# 2023-08-02_LVMi_Thermistors.net
KiCad netlist of a schematic drawn in EAGLE
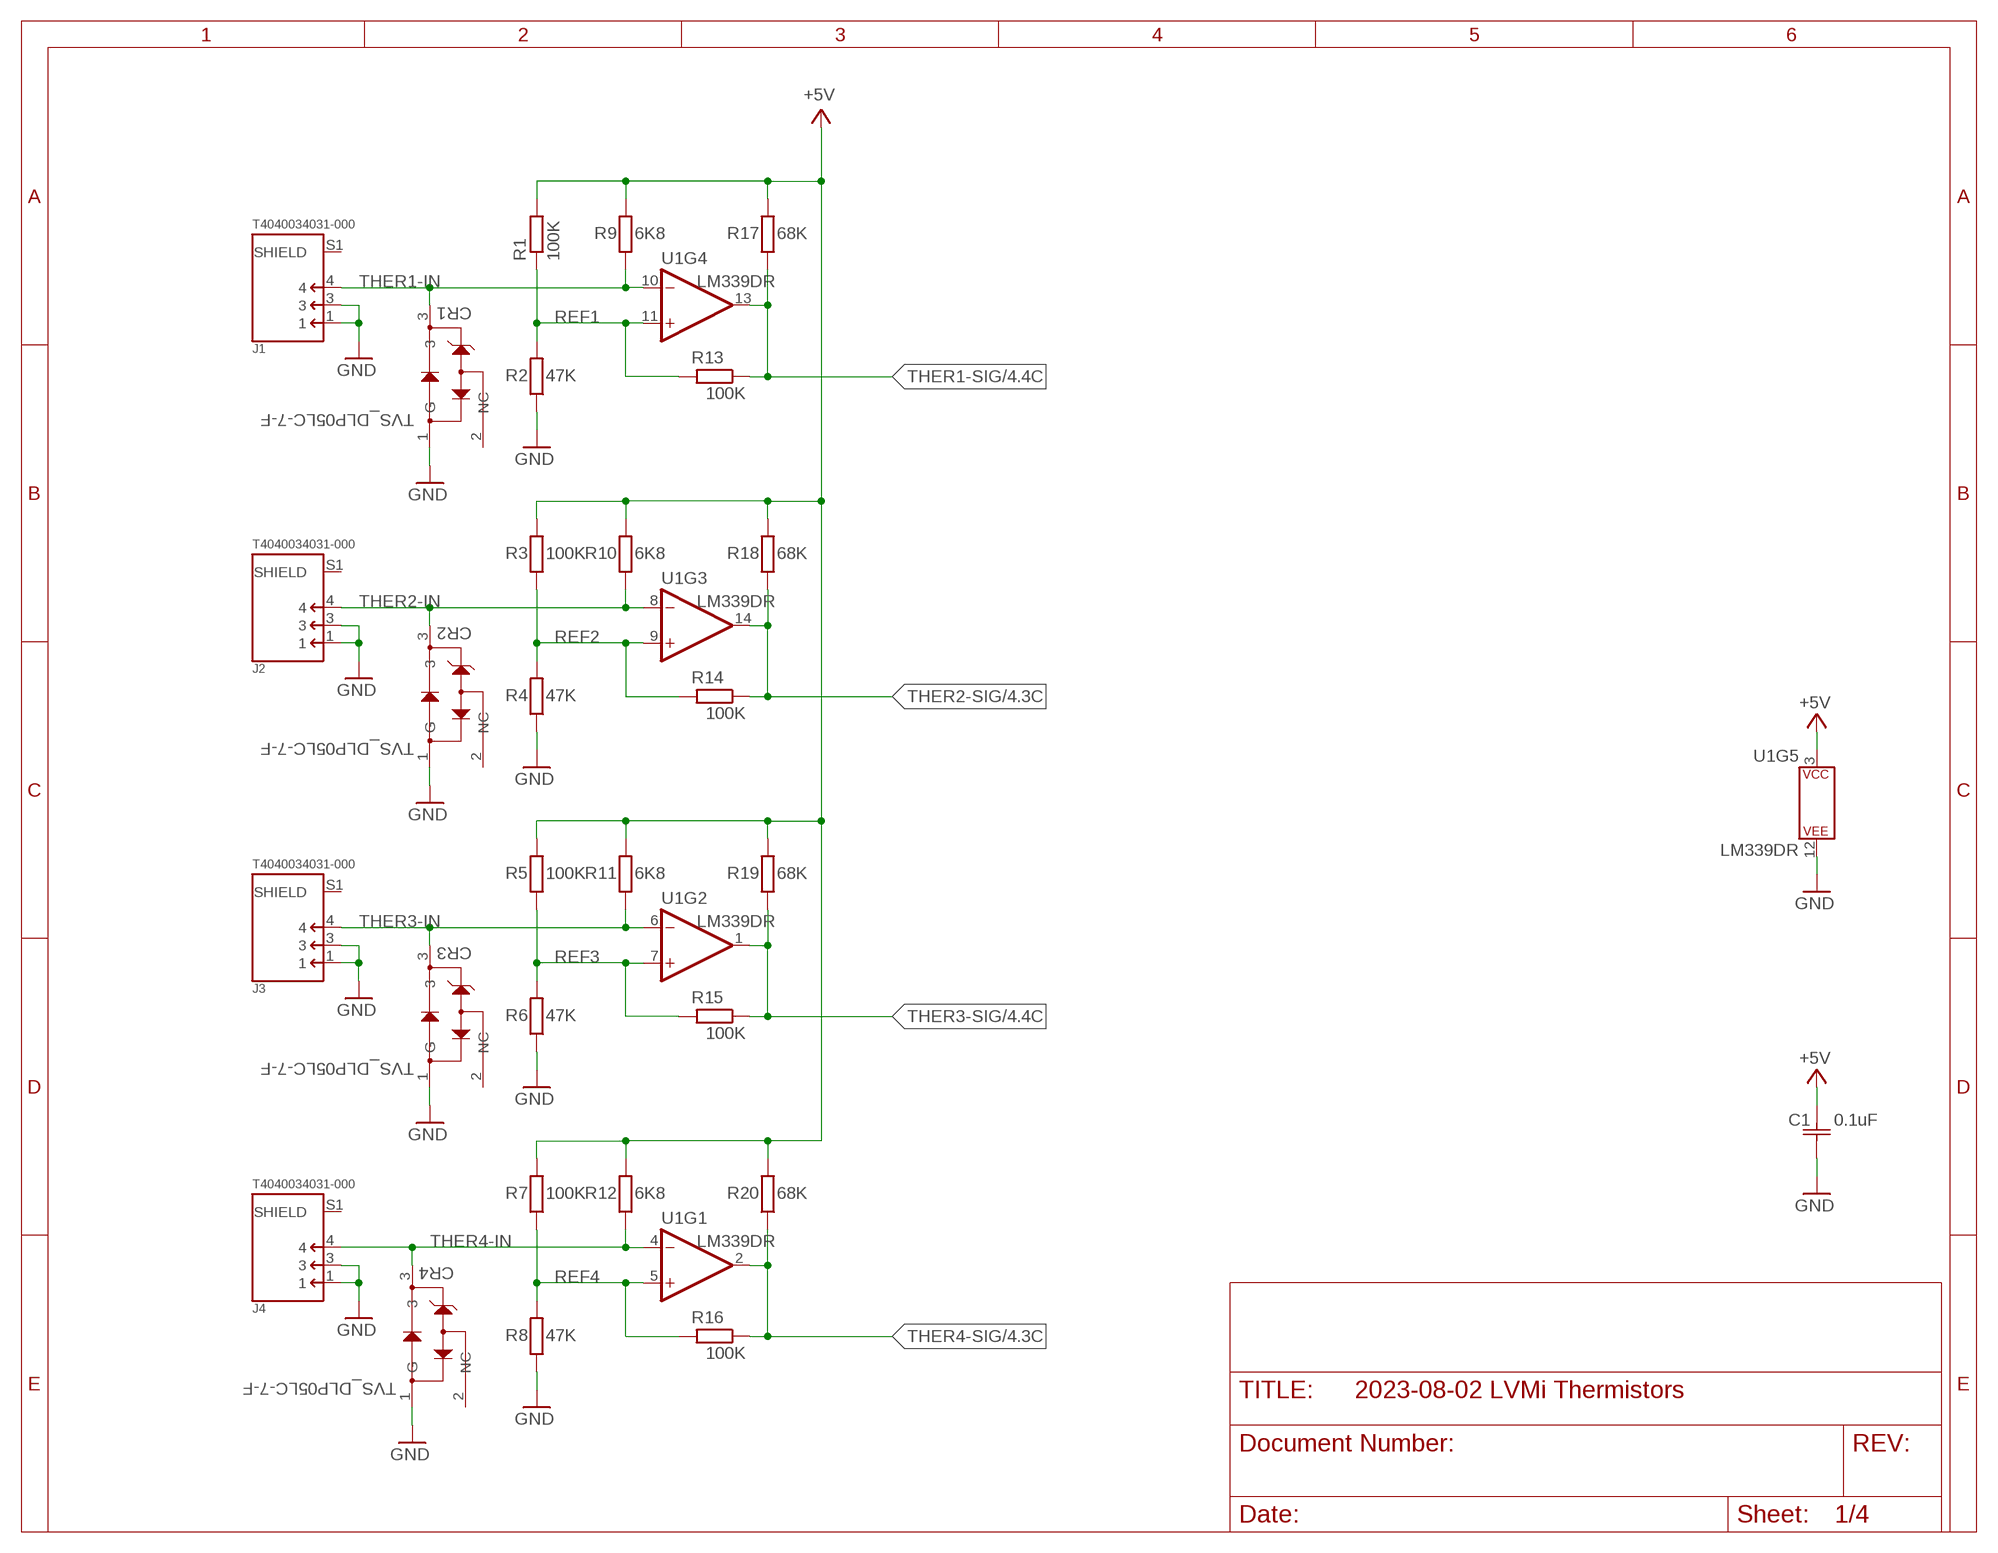
[diagram p0: schematic, sheet 1]
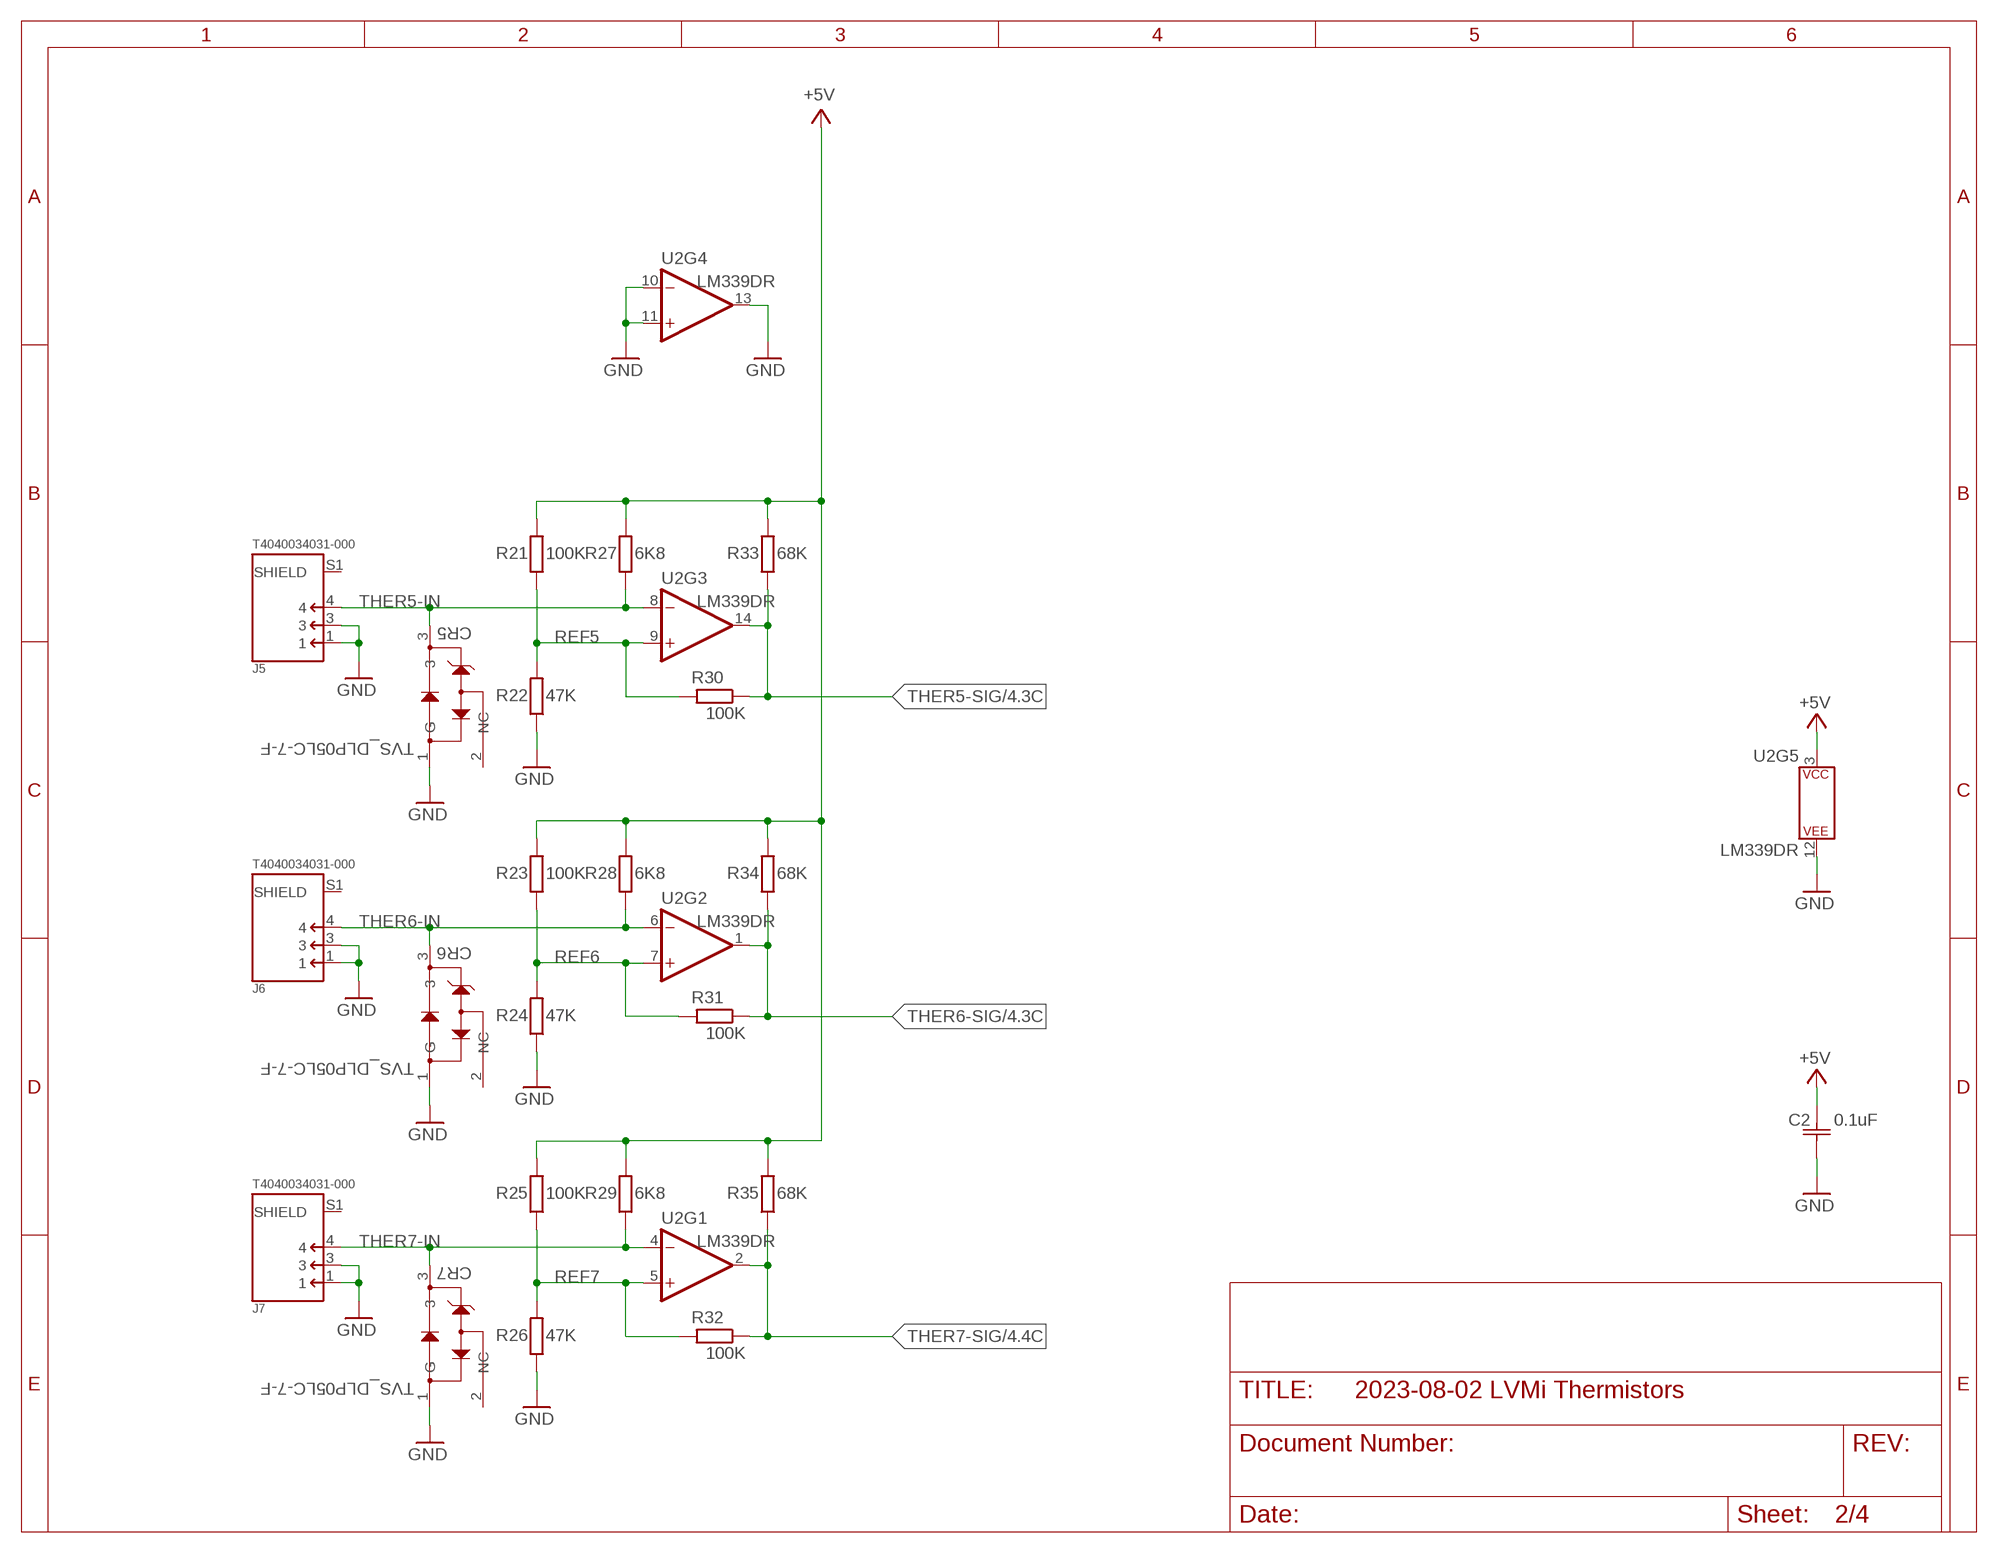
[diagram p1: schematic, sheet 2]
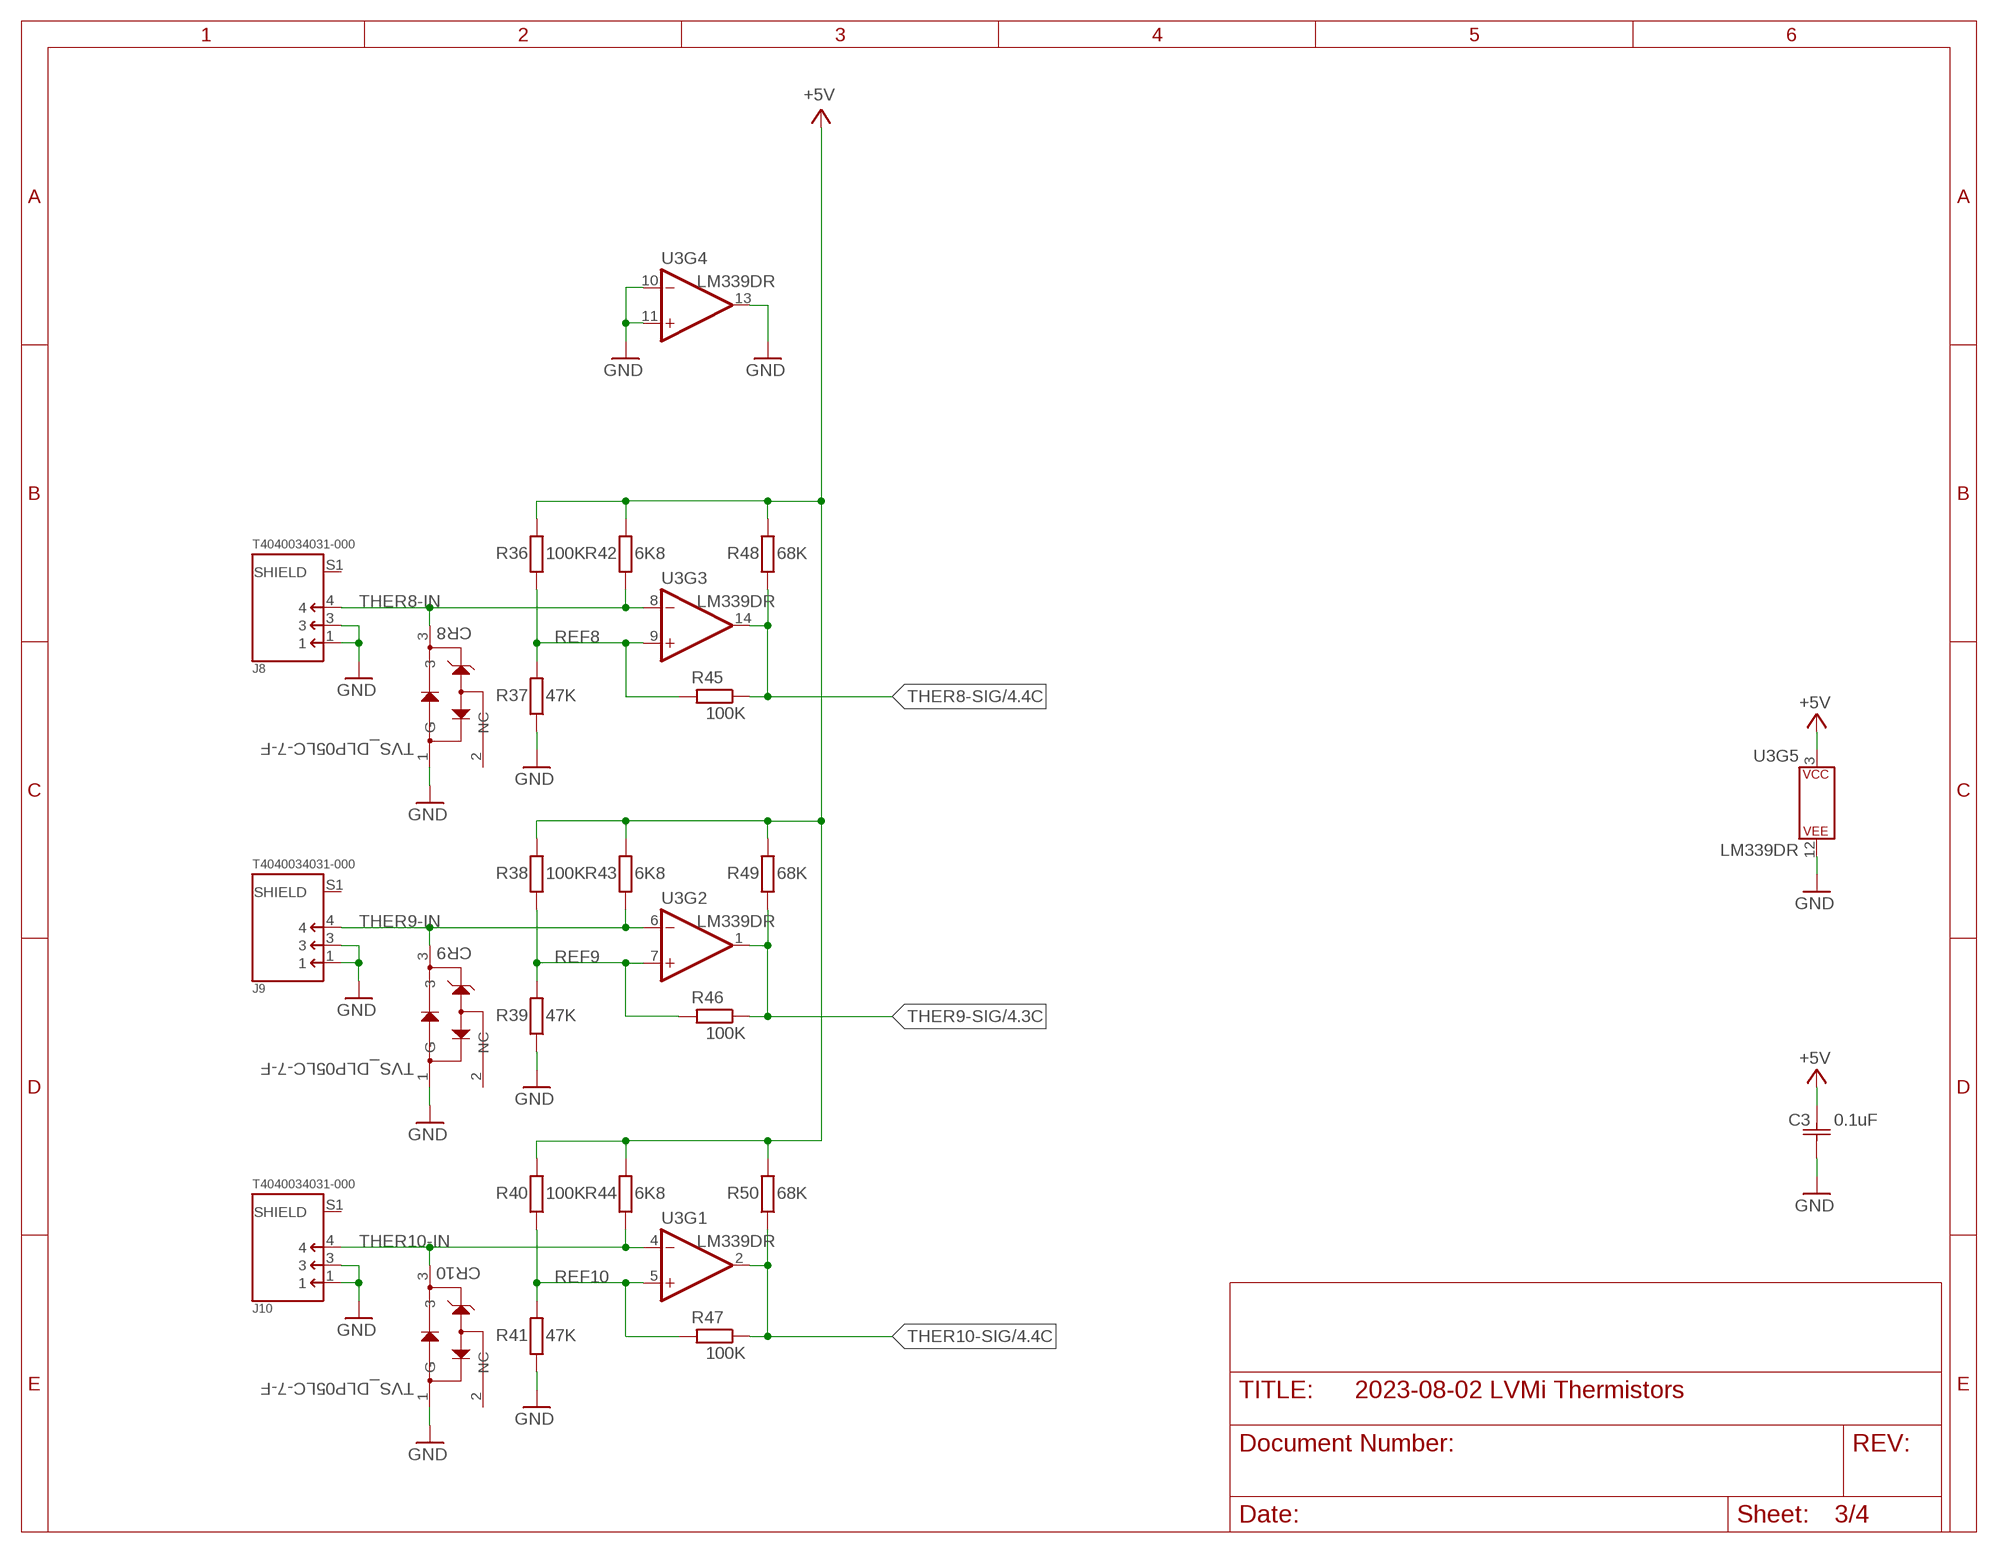
[diagram p2: schematic, sheet 3]
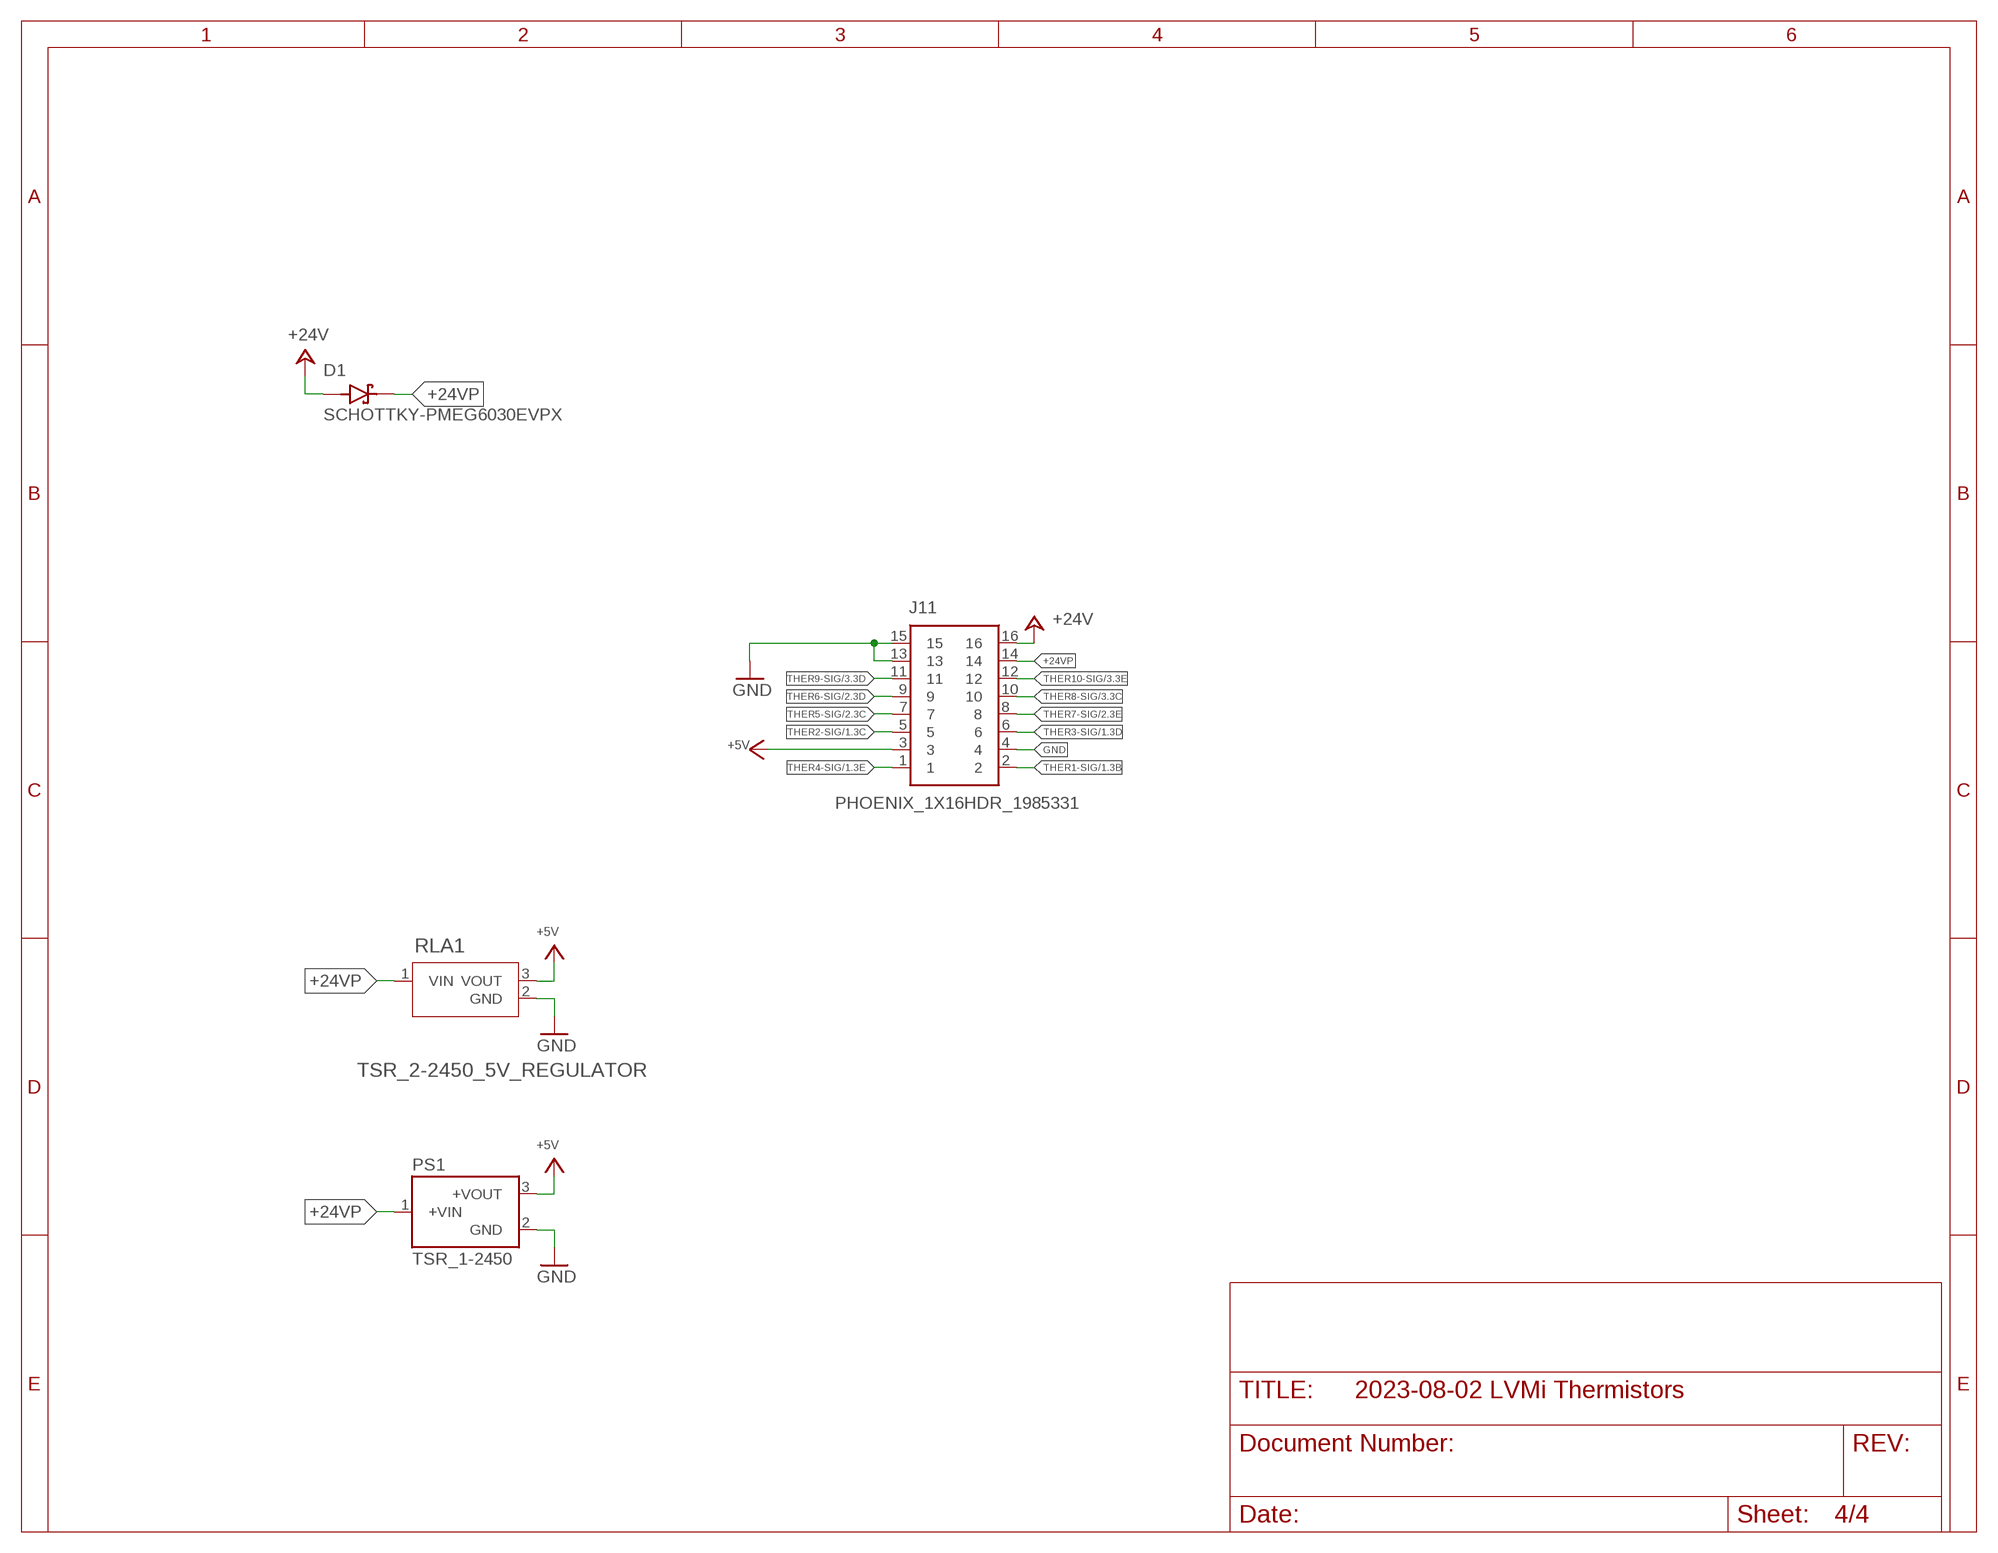
[diagram p3: schematic, sheet 4]

(export (version "E")
  (design (tool "Eeschema 10.0.6"))
  (components
    (comp (ref "D1")
      (value "SCHOTTKY-PMEG6030EVPX")
      (footprint "eagle-import:DIO_PMEG6030EVPX")
      (fields
        (field (name "DIGI-KEY_PART_NUMBER") "1727-1349-1-ND")
        (field (name "MF") "Nexperia USA")
        (field (name "MP") "PMEG6030EVPX")
      )
      (libsource (lib "eagle-import") (part "SCHOTTKY-PMEG6030EVPX"))
    )
    (comp (ref "J11")
      (value "PHOENIX_1X16HDR_1985331")
      (footprint "eagle-import:1985331")
      (fields
        (field (name "MANUFACTURER_PART_NUMBER") "1985331")
        (field (name "MOUSER_PART_NUMBER") "651-1985331")
      )
      (libsource (lib "eagle-import") (part "PHOENIX_1X16HDR_1985331"))
    )
    (comp (ref "PS1")
      (value "TSR_1-2450")
      (footprint "eagle-import:CONV_TSR_1-2450")
      (fields (field (name "MANUFACTURER") "Traco Power"))
      (libsource (lib "eagle-import") (part "TSR_1-2450"))
    )
    (comp (ref "RLA1")
      (value "TSR_2-2450_5V_REGULATOR")
      (footprint "eagle-import:TSR2-SINGLE_TRP")
      (fields
        (field (name "MANUFACTURER_PART_NUMBER") "TSR 2-2450")
        (field (name "COPYRIGHT") "Copyright (C) 2022 Ultra Librarian. All rights reserved.")
      )
      (libsource (lib "eagle-import") (part "TSR_2-2450_5V_REGULATOR"))
    )
    (comp (ref "C1")
      (value "0.1uF")
      (footprint "eagle-import:K104K15X7RF5TL2_VIS")
      (fields
        (field (name "MANUFACTURER_PART_NUMBER") "K104K15X7RF5TL2")
        (field (name "COPYRIGHT") "Copyright (C) 2023 Ultra Librarian. All rights reserved.")
      )
      (libsource (lib "eagle-import") (part "CAPTHRUHOLE"))
    )
    (comp (ref "CR1")
      (value "TVS_DLP05LC-7-F")
      (footprint "eagle-import:SOT23_DLP05LC_DIO")
      (fields
        (field (name "MANUFACTURER_PART_NUMBER") "DLP05LC-7-F")
        (field (name "COPYRIGHT") "Copyright (C) 2023 Ultra Librarian. All rights reserved.")
      )
      (libsource (lib "eagle-import") (part "TVS_DLP05LC-7-F"))
    )
    (comp (ref "CR2")
      (value "TVS_DLP05LC-7-F")
      (footprint "eagle-import:SOT23_DLP05LC_DIO")
      (fields
        (field (name "MANUFACTURER_PART_NUMBER") "DLP05LC-7-F")
        (field (name "COPYRIGHT") "Copyright (C) 2023 Ultra Librarian. All rights reserved.")
      )
      (libsource (lib "eagle-import") (part "TVS_DLP05LC-7-F"))
    )
    (comp (ref "CR3")
      (value "TVS_DLP05LC-7-F")
      (footprint "eagle-import:SOT23_DLP05LC_DIO")
      (fields
        (field (name "MANUFACTURER_PART_NUMBER") "DLP05LC-7-F")
        (field (name "COPYRIGHT") "Copyright (C) 2023 Ultra Librarian. All rights reserved.")
      )
      (libsource (lib "eagle-import") (part "TVS_DLP05LC-7-F"))
    )
    (comp (ref "CR4")
      (value "TVS_DLP05LC-7-F")
      (footprint "eagle-import:SOT23_DLP05LC_DIO")
      (fields
        (field (name "MANUFACTURER_PART_NUMBER") "DLP05LC-7-F")
        (field (name "COPYRIGHT") "Copyright (C) 2023 Ultra Librarian. All rights reserved.")
      )
      (libsource (lib "eagle-import") (part "TVS_DLP05LC-7-F"))
    )
    (comp (ref "J1")
      (value "T4040034031-000")
      (footprint "eagle-import:TE_T4040034031-000")
      (fields (field (name "MANUFACTURER") "TE "))
      (libsource (lib "eagle-import") (part "T4040034031-000"))
    )
    (comp (ref "J2")
      (value "T4040034031-000")
      (footprint "eagle-import:TE_T4040034031-000")
      (fields (field (name "MANUFACTURER") "TE "))
      (libsource (lib "eagle-import") (part "T4040034031-000"))
    )
    (comp (ref "J3")
      (value "T4040034031-000")
      (footprint "eagle-import:TE_T4040034031-000")
      (fields (field (name "MANUFACTURER") "TE "))
      (libsource (lib "eagle-import") (part "T4040034031-000"))
    )
    (comp (ref "J4")
      (value "T4040034031-000")
      (footprint "eagle-import:TE_T4040034031-000")
      (fields (field (name "MANUFACTURER") "TE "))
      (libsource (lib "eagle-import") (part "T4040034031-000"))
    )
    (comp (ref "R1")
      (value "100K")
      (footprint "eagle-import:0204_7")
      (libsource (lib "eagle-import") (part "R-EU_0204/7"))
    )
    (comp (ref "R2")
      (value "47K")
      (footprint "eagle-import:0204_7")
      (libsource (lib "eagle-import") (part "R-EU_0204/7"))
    )
    (comp (ref "R3")
      (value "100K")
      (footprint "eagle-import:0204_7")
      (libsource (lib "eagle-import") (part "R-EU_0204/7"))
    )
    (comp (ref "R4")
      (value "47K")
      (footprint "eagle-import:0204_7")
      (libsource (lib "eagle-import") (part "R-EU_0204/7"))
    )
    (comp (ref "R5")
      (value "100K")
      (footprint "eagle-import:0204_7")
      (libsource (lib "eagle-import") (part "R-EU_0204/7"))
    )
    (comp (ref "R6")
      (value "47K")
      (footprint "eagle-import:0204_7")
      (libsource (lib "eagle-import") (part "R-EU_0204/7"))
    )
    (comp (ref "R7")
      (value "100K")
      (footprint "eagle-import:0204_7")
      (libsource (lib "eagle-import") (part "R-EU_0204/7"))
    )
    (comp (ref "R8")
      (value "47K")
      (footprint "eagle-import:0204_7")
      (libsource (lib "eagle-import") (part "R-EU_0204/7"))
    )
    (comp (ref "R9")
      (value "6K8")
      (footprint "eagle-import:0204_7")
      (libsource (lib "eagle-import") (part "R-EU_0204/7"))
    )
    (comp (ref "R10")
      (value "6K8")
      (footprint "eagle-import:0204_7")
      (libsource (lib "eagle-import") (part "R-EU_0204/7"))
    )
    (comp (ref "R11")
      (value "6K8")
      (footprint "eagle-import:0204_7")
      (libsource (lib "eagle-import") (part "R-EU_0204/7"))
    )
    (comp (ref "R12")
      (value "6K8")
      (footprint "eagle-import:0204_7")
      (libsource (lib "eagle-import") (part "R-EU_0204/7"))
    )
    (comp (ref "R13")
      (value "100K")
      (footprint "eagle-import:0204_7")
      (libsource (lib "eagle-import") (part "R-EU_0204/7"))
    )
    (comp (ref "R14")
      (value "100K")
      (footprint "eagle-import:0204_7")
      (libsource (lib "eagle-import") (part "R-EU_0204/7"))
    )
    (comp (ref "R15")
      (value "100K")
      (footprint "eagle-import:0204_7")
      (libsource (lib "eagle-import") (part "R-EU_0204/7"))
    )
    (comp (ref "R16")
      (value "100K")
      (footprint "eagle-import:0204_7")
      (libsource (lib "eagle-import") (part "R-EU_0204/7"))
    )
    (comp (ref "R17")
      (value "68K")
      (footprint "eagle-import:0204_7")
      (libsource (lib "eagle-import") (part "R-EU_0204/7"))
    )
    (comp (ref "R18")
      (value "68K")
      (footprint "eagle-import:0204_7")
      (libsource (lib "eagle-import") (part "R-EU_0204/7"))
    )
    (comp (ref "R19")
      (value "68K")
      (footprint "eagle-import:0204_7")
      (libsource (lib "eagle-import") (part "R-EU_0204/7"))
    )
    (comp (ref "R20")
      (value "68K")
      (footprint "eagle-import:0204_7")
      (libsource (lib "eagle-import") (part "R-EU_0204/7"))
    )
    (comp (ref "U1")
      (value "LM339DR")
      (footprint "eagle-import:SOIC127P599X175-14")
      (libsource (lib "eagle-import") (part "LM339SOIC-14"))
    )
    (comp (ref "C2")
      (value "0.1uF")
      (footprint "eagle-import:K104K15X7RF5TL2_VIS")
      (fields
        (field (name "MANUFACTURER_PART_NUMBER") "K104K15X7RF5TL2")
        (field (name "COPYRIGHT") "Copyright (C) 2023 Ultra Librarian. All rights reserved.")
      )
      (libsource (lib "eagle-import") (part "CAPTHRUHOLE"))
    )
    (comp (ref "CR5")
      (value "TVS_DLP05LC-7-F")
      (footprint "eagle-import:SOT23_DLP05LC_DIO")
      (fields
        (field (name "MANUFACTURER_PART_NUMBER") "DLP05LC-7-F")
        (field (name "COPYRIGHT") "Copyright (C) 2023 Ultra Librarian. All rights reserved.")
      )
      (libsource (lib "eagle-import") (part "TVS_DLP05LC-7-F"))
    )
    (comp (ref "CR6")
      (value "TVS_DLP05LC-7-F")
      (footprint "eagle-import:SOT23_DLP05LC_DIO")
      (fields
        (field (name "MANUFACTURER_PART_NUMBER") "DLP05LC-7-F")
        (field (name "COPYRIGHT") "Copyright (C) 2023 Ultra Librarian. All rights reserved.")
      )
      (libsource (lib "eagle-import") (part "TVS_DLP05LC-7-F"))
    )
    (comp (ref "CR7")
      (value "TVS_DLP05LC-7-F")
      (footprint "eagle-import:SOT23_DLP05LC_DIO")
      (fields
        (field (name "MANUFACTURER_PART_NUMBER") "DLP05LC-7-F")
        (field (name "COPYRIGHT") "Copyright (C) 2023 Ultra Librarian. All rights reserved.")
      )
      (libsource (lib "eagle-import") (part "TVS_DLP05LC-7-F"))
    )
    (comp (ref "J5")
      (value "T4040034031-000")
      (footprint "eagle-import:TE_T4040034031-000")
      (fields (field (name "MANUFACTURER") "TE "))
      (libsource (lib "eagle-import") (part "T4040034031-000"))
    )
    (comp (ref "J6")
      (value "T4040034031-000")
      (footprint "eagle-import:TE_T4040034031-000")
      (fields (field (name "MANUFACTURER") "TE "))
      (libsource (lib "eagle-import") (part "T4040034031-000"))
    )
    (comp (ref "J7")
      (value "T4040034031-000")
      (footprint "eagle-import:TE_T4040034031-000")
      (fields (field (name "MANUFACTURER") "TE "))
      (libsource (lib "eagle-import") (part "T4040034031-000"))
    )
    (comp (ref "R21")
      (value "100K")
      (footprint "eagle-import:0204_7")
      (libsource (lib "eagle-import") (part "R-EU_0204/7"))
    )
    (comp (ref "R22")
      (value "47K")
      (footprint "eagle-import:0204_7")
      (libsource (lib "eagle-import") (part "R-EU_0204/7"))
    )
    (comp (ref "R23")
      (value "100K")
      (footprint "eagle-import:0204_7")
      (libsource (lib "eagle-import") (part "R-EU_0204/7"))
    )
    (comp (ref "R24")
      (value "47K")
      (footprint "eagle-import:0204_7")
      (libsource (lib "eagle-import") (part "R-EU_0204/7"))
    )
    (comp (ref "R25")
      (value "100K")
      (footprint "eagle-import:0204_7")
      (libsource (lib "eagle-import") (part "R-EU_0204/7"))
    )
    (comp (ref "R26")
      (value "47K")
      (footprint "eagle-import:0204_7")
      (libsource (lib "eagle-import") (part "R-EU_0204/7"))
    )
    (comp (ref "R27")
      (value "6K8")
      (footprint "eagle-import:0204_7")
      (libsource (lib "eagle-import") (part "R-EU_0204/7"))
    )
    (comp (ref "R28")
      (value "6K8")
      (footprint "eagle-import:0204_7")
      (libsource (lib "eagle-import") (part "R-EU_0204/7"))
    )
    (comp (ref "R29")
      (value "6K8")
      (footprint "eagle-import:0204_7")
      (libsource (lib "eagle-import") (part "R-EU_0204/7"))
    )
    (comp (ref "R30")
      (value "100K")
      (footprint "eagle-import:0204_7")
      (libsource (lib "eagle-import") (part "R-EU_0204/7"))
    )
    (comp (ref "R31")
      (value "100K")
      (footprint "eagle-import:0204_7")
      (libsource (lib "eagle-import") (part "R-EU_0204/7"))
    )
    (comp (ref "R32")
      (value "100K")
      (footprint "eagle-import:0204_7")
      (libsource (lib "eagle-import") (part "R-EU_0204/7"))
    )
    (comp (ref "R33")
      (value "68K")
      (footprint "eagle-import:0204_7")
      (libsource (lib "eagle-import") (part "R-EU_0204/7"))
    )
    (comp (ref "R34")
      (value "68K")
      (footprint "eagle-import:0204_7")
      (libsource (lib "eagle-import") (part "R-EU_0204/7"))
    )
    (comp (ref "R35")
      (value "68K")
      (footprint "eagle-import:0204_7")
      (libsource (lib "eagle-import") (part "R-EU_0204/7"))
    )
    (comp (ref "U2")
      (value "LM339DR")
      (footprint "eagle-import:SOIC127P599X175-14")
      (libsource (lib "eagle-import") (part "LM339SOIC-14"))
    )
    (comp (ref "C3")
      (value "0.1uF")
      (footprint "eagle-import:K104K15X7RF5TL2_VIS")
      (fields
        (field (name "MANUFACTURER_PART_NUMBER") "K104K15X7RF5TL2")
        (field (name "COPYRIGHT") "Copyright (C) 2023 Ultra Librarian. All rights reserved.")
      )
      (libsource (lib "eagle-import") (part "CAPTHRUHOLE"))
    )
    (comp (ref "CR8")
      (value "TVS_DLP05LC-7-F")
      (footprint "eagle-import:SOT23_DLP05LC_DIO")
      (fields
        (field (name "MANUFACTURER_PART_NUMBER") "DLP05LC-7-F")
        (field (name "COPYRIGHT") "Copyright (C) 2023 Ultra Librarian. All rights reserved.")
      )
      (libsource (lib "eagle-import") (part "TVS_DLP05LC-7-F"))
    )
    (comp (ref "CR9")
      (value "TVS_DLP05LC-7-F")
      (footprint "eagle-import:SOT23_DLP05LC_DIO")
      (fields
        (field (name "MANUFACTURER_PART_NUMBER") "DLP05LC-7-F")
        (field (name "COPYRIGHT") "Copyright (C) 2023 Ultra Librarian. All rights reserved.")
      )
      (libsource (lib "eagle-import") (part "TVS_DLP05LC-7-F"))
    )
    (comp (ref "CR10")
      (value "TVS_DLP05LC-7-F")
      (footprint "eagle-import:SOT23_DLP05LC_DIO")
      (fields
        (field (name "MANUFACTURER_PART_NUMBER") "DLP05LC-7-F")
        (field (name "COPYRIGHT") "Copyright (C) 2023 Ultra Librarian. All rights reserved.")
      )
      (libsource (lib "eagle-import") (part "TVS_DLP05LC-7-F"))
    )
    (comp (ref "J8")
      (value "T4040034031-000")
      (footprint "eagle-import:TE_T4040034031-000")
      (fields (field (name "MANUFACTURER") "TE "))
      (libsource (lib "eagle-import") (part "T4040034031-000"))
    )
    (comp (ref "J9")
      (value "T4040034031-000")
      (footprint "eagle-import:TE_T4040034031-000")
      (fields (field (name "MANUFACTURER") "TE "))
      (libsource (lib "eagle-import") (part "T4040034031-000"))
    )
    (comp (ref "J10")
      (value "T4040034031-000")
      (footprint "eagle-import:TE_T4040034031-000")
      (fields (field (name "MANUFACTURER") "TE "))
      (libsource (lib "eagle-import") (part "T4040034031-000"))
    )
    (comp (ref "R36")
      (value "100K")
      (footprint "eagle-import:0204_7")
      (libsource (lib "eagle-import") (part "R-EU_0204/7"))
    )
    (comp (ref "R37")
      (value "47K")
      (footprint "eagle-import:0204_7")
      (libsource (lib "eagle-import") (part "R-EU_0204/7"))
    )
    (comp (ref "R38")
      (value "100K")
      (footprint "eagle-import:0204_7")
      (libsource (lib "eagle-import") (part "R-EU_0204/7"))
    )
    (comp (ref "R39")
      (value "47K")
      (footprint "eagle-import:0204_7")
      (libsource (lib "eagle-import") (part "R-EU_0204/7"))
    )
    (comp (ref "R40")
      (value "100K")
      (footprint "eagle-import:0204_7")
      (libsource (lib "eagle-import") (part "R-EU_0204/7"))
    )
    (comp (ref "R41")
      (value "47K")
      (footprint "eagle-import:0204_7")
      (libsource (lib "eagle-import") (part "R-EU_0204/7"))
    )
    (comp (ref "R42")
      (value "6K8")
      (footprint "eagle-import:0204_7")
      (libsource (lib "eagle-import") (part "R-EU_0204/7"))
    )
    (comp (ref "R43")
      (value "6K8")
      (footprint "eagle-import:0204_7")
      (libsource (lib "eagle-import") (part "R-EU_0204/7"))
    )
    (comp (ref "R44")
      (value "6K8")
      (footprint "eagle-import:0204_7")
      (libsource (lib "eagle-import") (part "R-EU_0204/7"))
    )
    (comp (ref "R45")
      (value "100K")
      (footprint "eagle-import:0204_7")
      (libsource (lib "eagle-import") (part "R-EU_0204/7"))
    )
    (comp (ref "R46")
      (value "100K")
      (footprint "eagle-import:0204_7")
      (libsource (lib "eagle-import") (part "R-EU_0204/7"))
    )
    (comp (ref "R47")
      (value "100K")
      (footprint "eagle-import:0204_7")
      (libsource (lib "eagle-import") (part "R-EU_0204/7"))
    )
    (comp (ref "R48")
      (value "68K")
      (footprint "eagle-import:0204_7")
      (libsource (lib "eagle-import") (part "R-EU_0204/7"))
    )
    (comp (ref "R49")
      (value "68K")
      (footprint "eagle-import:0204_7")
      (libsource (lib "eagle-import") (part "R-EU_0204/7"))
    )
    (comp (ref "R50")
      (value "68K")
      (footprint "eagle-import:0204_7")
      (libsource (lib "eagle-import") (part "R-EU_0204/7"))
    )
    (comp (ref "U3")
      (value "LM339DR")
      (footprint "eagle-import:SOIC127P599X175-14")
      (libsource (lib "eagle-import") (part "LM339SOIC-14"))
    )
  )
  (nets
    (net (code "1") (name "+5V") (class "Default")
      (node (ref "C1") (pin "2") (pinfunction "2_2") (pintype "passive"))
      (node (ref "C2") (pin "2") (pinfunction "2_2") (pintype "passive"))
      (node (ref "C3") (pin "2") (pinfunction "2_2") (pintype "passive"))
      (node (ref "J11") (pin "3") (pinfunction "3_3") (pintype "bidirectional"))
      (node (ref "PS1") (pin "3") (pinfunction "+VOUT_3") (pintype "output"))
      (node (ref "R1") (pin "2") (pinfunction "2_2") (pintype "passive"))
      (node (ref "R10") (pin "2") (pinfunction "2_2") (pintype "passive"))
      (node (ref "R11") (pin "2") (pinfunction "2_2") (pintype "passive"))
      (node (ref "R12") (pin "2") (pinfunction "2_2") (pintype "passive"))
      (node (ref "R17") (pin "2") (pinfunction "2_2") (pintype "passive"))
      (node (ref "R18") (pin "2") (pinfunction "2_2") (pintype "passive"))
      (node (ref "R19") (pin "2") (pinfunction "2_2") (pintype "passive"))
      (node (ref "R20") (pin "2") (pinfunction "2_2") (pintype "passive"))
      (node (ref "R21") (pin "2") (pinfunction "2_2") (pintype "passive"))
      (node (ref "R23") (pin "2") (pinfunction "2_2") (pintype "passive"))
      (node (ref "R25") (pin "2") (pinfunction "2_2") (pintype "passive"))
      (node (ref "R27") (pin "2") (pinfunction "2_2") (pintype "passive"))
      (node (ref "R28") (pin "2") (pinfunction "2_2") (pintype "passive"))
      (node (ref "R29") (pin "2") (pinfunction "2_2") (pintype "passive"))
      (node (ref "R3") (pin "2") (pinfunction "2_2") (pintype "passive"))
      (node (ref "R33") (pin "2") (pinfunction "2_2") (pintype "passive"))
      (node (ref "R34") (pin "2") (pinfunction "2_2") (pintype "passive"))
      (node (ref "R35") (pin "2") (pinfunction "2_2") (pintype "passive"))
      (node (ref "R36") (pin "2") (pinfunction "2_2") (pintype "passive"))
      (node (ref "R38") (pin "2") (pinfunction "2_2") (pintype "passive"))
      (node (ref "R40") (pin "2") (pinfunction "2_2") (pintype "passive"))
      (node (ref "R42") (pin "2") (pinfunction "2_2") (pintype "passive"))
      (node (ref "R43") (pin "2") (pinfunction "2_2") (pintype "passive"))
      (node (ref "R44") (pin "2") (pinfunction "2_2") (pintype "passive"))
      (node (ref "R48") (pin "2") (pinfunction "2_2") (pintype "passive"))
      (node (ref "R49") (pin "2") (pinfunction "2_2") (pintype "passive"))
      (node (ref "R5") (pin "2") (pinfunction "2_2") (pintype "passive"))
      (node (ref "R50") (pin "2") (pinfunction "2_2") (pintype "passive"))
      (node (ref "R7") (pin "2") (pinfunction "2_2") (pintype "passive"))
      (node (ref "R9") (pin "2") (pinfunction "2_2") (pintype "passive"))
      (node (ref "RLA1") (pin "3") (pinfunction "VOUT_3") (pintype "passive"))
      (node (ref "U1") (pin "3") (pinfunction "P$V+_3") (pintype "bidirectional"))
      (node (ref "U2") (pin "3") (pinfunction "P$V+_3") (pintype "bidirectional"))
      (node (ref "U3") (pin "3") (pinfunction "P$V+_3") (pintype "bidirectional"))
    )
    (net (code "2") (name "+24V") (class "Default")
      (node (ref "D1") (pin "2") (pinfunction "A_2") (pintype "passive"))
      (node (ref "J11") (pin "16") (pinfunction "16_16") (pintype "bidirectional"))
    )
    (net (code "3") (name "+24VP") (class "Default")
      (node (ref "D1") (pin "1") (pinfunction "K_1") (pintype "passive"))
      (node (ref "J11") (pin "14") (pinfunction "14_14") (pintype "bidirectional"))
      (node (ref "PS1") (pin "1") (pinfunction "+VIN_1") (pintype "input"))
      (node (ref "RLA1") (pin "1") (pinfunction "VIN_1") (pintype "passive"))
    )
    (net (code "4") (name "GND") (class "Default")
      (node (ref "C1") (pin "1") (pinfunction "1_1") (pintype "passive"))
      (node (ref "C2") (pin "1") (pinfunction "1_1") (pintype "passive"))
      (node (ref "C3") (pin "1") (pinfunction "1_1") (pintype "passive"))
      (node (ref "CR1") (pin "1") (pinfunction "G_1") (pintype "passive"))
      (node (ref "CR10") (pin "1") (pinfunction "G_1") (pintype "passive"))
      (node (ref "CR2") (pin "1") (pinfunction "G_1") (pintype "passive"))
      (node (ref "CR3") (pin "1") (pinfunction "G_1") (pintype "passive"))
      (node (ref "CR4") (pin "1") (pinfunction "G_1") (pintype "passive"))
      (node (ref "CR5") (pin "1") (pinfunction "G_1") (pintype "passive"))
      (node (ref "CR6") (pin "1") (pinfunction "G_1") (pintype "passive"))
      (node (ref "CR7") (pin "1") (pinfunction "G_1") (pintype "passive"))
      (node (ref "CR8") (pin "1") (pinfunction "G_1") (pintype "passive"))
      (node (ref "CR9") (pin "1") (pinfunction "G_1") (pintype "passive"))
      (node (ref "J1") (pin "1") (pinfunction "1_1") (pintype "passive"))
      (node (ref "J1") (pin "3") (pinfunction "3_3") (pintype "passive"))
      (node (ref "J10") (pin "1") (pinfunction "1_1") (pintype "passive"))
      (node (ref "J10") (pin "3") (pinfunction "3_3") (pintype "passive"))
      (node (ref "J11") (pin "13") (pinfunction "13_13") (pintype "bidirectional"))
      (node (ref "J11") (pin "15") (pinfunction "15_15") (pintype "bidirectional"))
      (node (ref "J11") (pin "4") (pinfunction "4_4") (pintype "bidirectional"))
      (node (ref "J2") (pin "1") (pinfunction "1_1") (pintype "passive"))
      (node (ref "J2") (pin "3") (pinfunction "3_3") (pintype "passive"))
      (node (ref "J3") (pin "1") (pinfunction "1_1") (pintype "passive"))
      (node (ref "J3") (pin "3") (pinfunction "3_3") (pintype "passive"))
      (node (ref "J4") (pin "1") (pinfunction "1_1") (pintype "passive"))
      (node (ref "J4") (pin "3") (pinfunction "3_3") (pintype "passive"))
      (node (ref "J5") (pin "1") (pinfunction "1_1") (pintype "passive"))
      (node (ref "J5") (pin "3") (pinfunction "3_3") (pintype "passive"))
      (node (ref "J6") (pin "1") (pinfunction "1_1") (pintype "passive"))
      (node (ref "J6") (pin "3") (pinfunction "3_3") (pintype "passive"))
      (node (ref "J7") (pin "1") (pinfunction "1_1") (pintype "passive"))
      (node (ref "J7") (pin "3") (pinfunction "3_3") (pintype "passive"))
      (node (ref "J8") (pin "1") (pinfunction "1_1") (pintype "passive"))
      (node (ref "J8") (pin "3") (pinfunction "3_3") (pintype "passive"))
      (node (ref "J9") (pin "1") (pinfunction "1_1") (pintype "passive"))
      (node (ref "J9") (pin "3") (pinfunction "3_3") (pintype "passive"))
      (node (ref "PS1") (pin "2") (pinfunction "GND_2") (pintype "power_in"))
      (node (ref "R2") (pin "1") (pinfunction "1_1") (pintype "passive"))
      (node (ref "R22") (pin "1") (pinfunction "1_1") (pintype "passive"))
      (node (ref "R24") (pin "1") (pinfunction "1_1") (pintype "passive"))
      (node (ref "R26") (pin "1") (pinfunction "1_1") (pintype "passive"))
      (node (ref "R37") (pin "1") (pinfunction "1_1") (pintype "passive"))
      (node (ref "R39") (pin "1") (pinfunction "1_1") (pintype "passive"))
      (node (ref "R4") (pin "1") (pinfunction "1_1") (pintype "passive"))
      (node (ref "R41") (pin "1") (pinfunction "1_1") (pintype "passive"))
      (node (ref "R6") (pin "1") (pinfunction "1_1") (pintype "passive"))
      (node (ref "R8") (pin "1") (pinfunction "1_1") (pintype "passive"))
      (node (ref "RLA1") (pin "2") (pinfunction "GND_2") (pintype "passive"))
      (node (ref "U1") (pin "12") (pinfunction "P$V-_12") (pintype "bidirectional"))
      (node (ref "U2") (pin "10") (pinfunction "-IN_10") (pintype "input"))
      (node (ref "U2") (pin "11") (pinfunction "+IN_11") (pintype "input"))
      (node (ref "U2") (pin "12") (pinfunction "P$V-_12") (pintype "bidirectional"))
      (node (ref "U2") (pin "13") (pinfunction "OUT_13") (pintype "output"))
      (node (ref "U3") (pin "10") (pinfunction "-IN_10") (pintype "input"))
      (node (ref "U3") (pin "11") (pinfunction "+IN_11") (pintype "input"))
      (node (ref "U3") (pin "12") (pinfunction "P$V-_12") (pintype "bidirectional"))
      (node (ref "U3") (pin "13") (pinfunction "OUT_13") (pintype "output"))
    )
    (net (code "5") (name "REF1") (class "Default")
      (node (ref "R1") (pin "1") (pinfunction "1_1") (pintype "passive"))
      (node (ref "R13") (pin "2") (pinfunction "2_2") (pintype "passive"))
      (node (ref "R2") (pin "2") (pinfunction "2_2") (pintype "passive"))
      (node (ref "U1") (pin "11") (pinfunction "+IN_11") (pintype "input"))
    )
    (net (code "6") (name "REF2") (class "Default")
      (node (ref "R14") (pin "2") (pinfunction "2_2") (pintype "passive"))
      (node (ref "R3") (pin "1") (pinfunction "1_1") (pintype "passive"))
      (node (ref "R4") (pin "2") (pinfunction "2_2") (pintype "passive"))
      (node (ref "U1") (pin "9") (pinfunction "+IN_9") (pintype "input"))
    )
    (net (code "7") (name "REF3") (class "Default")
      (node (ref "R15") (pin "2") (pinfunction "2_2") (pintype "passive"))
      (node (ref "R5") (pin "1") (pinfunction "1_1") (pintype "passive"))
      (node (ref "R6") (pin "2") (pinfunction "2_2") (pintype "passive"))
      (node (ref "U1") (pin "7") (pinfunction "+IN_7") (pintype "input"))
    )
    (net (code "8") (name "REF4") (class "Default")
      (node (ref "R16") (pin "2") (pinfunction "2_2") (pintype "passive"))
      (node (ref "R7") (pin "1") (pinfunction "1_1") (pintype "passive"))
      (node (ref "R8") (pin "2") (pinfunction "2_2") (pintype "passive"))
      (node (ref "U1") (pin "5") (pinfunction "+IN_5") (pintype "input"))
    )
    (net (code "9") (name "REF5") (class "Default")
      (node (ref "R21") (pin "1") (pinfunction "1_1") (pintype "passive"))
      (node (ref "R22") (pin "2") (pinfunction "2_2") (pintype "passive"))
      (node (ref "R30") (pin "2") (pinfunction "2_2") (pintype "passive"))
      (node (ref "U2") (pin "9") (pinfunction "+IN_9") (pintype "input"))
    )
    (net (code "10") (name "REF6") (class "Default")
      (node (ref "R23") (pin "1") (pinfunction "1_1") (pintype "passive"))
      (node (ref "R24") (pin "2") (pinfunction "2_2") (pintype "passive"))
      (node (ref "R31") (pin "2") (pinfunction "2_2") (pintype "passive"))
      (node (ref "U2") (pin "7") (pinfunction "+IN_7") (pintype "input"))
    )
    (net (code "11") (name "REF7") (class "Default")
      (node (ref "R25") (pin "1") (pinfunction "1_1") (pintype "passive"))
      (node (ref "R26") (pin "2") (pinfunction "2_2") (pintype "passive"))
      (node (ref "R32") (pin "2") (pinfunction "2_2") (pintype "passive"))
      (node (ref "U2") (pin "5") (pinfunction "+IN_5") (pintype "input"))
    )
    (net (code "12") (name "REF8") (class "Default")
      (node (ref "R36") (pin "1") (pinfunction "1_1") (pintype "passive"))
      (node (ref "R37") (pin "2") (pinfunction "2_2") (pintype "passive"))
      (node (ref "R45") (pin "2") (pinfunction "2_2") (pintype "passive"))
      (node (ref "U3") (pin "9") (pinfunction "+IN_9") (pintype "input"))
    )
    (net (code "13") (name "REF9") (class "Default")
      (node (ref "R38") (pin "1") (pinfunction "1_1") (pintype "passive"))
      (node (ref "R39") (pin "2") (pinfunction "2_2") (pintype "passive"))
      (node (ref "R46") (pin "2") (pinfunction "2_2") (pintype "passive"))
      (node (ref "U3") (pin "7") (pinfunction "+IN_7") (pintype "input"))
    )
    (net (code "14") (name "REF10") (class "Default")
      (node (ref "R40") (pin "1") (pinfunction "1_1") (pintype "passive"))
      (node (ref "R41") (pin "2") (pinfunction "2_2") (pintype "passive"))
      (node (ref "R47") (pin "2") (pinfunction "2_2") (pintype "passive"))
      (node (ref "U3") (pin "5") (pinfunction "+IN_5") (pintype "input"))
    )
    (net (code "15") (name "THER1-IN") (class "Default")
      (node (ref "CR1") (pin "3") (pinfunction "3_3") (pintype "passive"))
      (node (ref "J1") (pin "4") (pinfunction "4_4") (pintype "passive"))
      (node (ref "R9") (pin "1") (pinfunction "1_1") (pintype "passive"))
      (node (ref "U1") (pin "10") (pinfunction "-IN_10") (pintype "input"))
    )
    (net (code "16") (name "THER1-SIG") (class "Default")
      (node (ref "J11") (pin "2") (pinfunction "2_2") (pintype "bidirectional"))
      (node (ref "R13") (pin "1") (pinfunction "1_1") (pintype "passive"))
      (node (ref "R17") (pin "1") (pinfunction "1_1") (pintype "passive"))
      (node (ref "U1") (pin "13") (pinfunction "OUT_13") (pintype "output"))
    )
    (net (code "17") (name "THER2-IN") (class "Default")
      (node (ref "CR2") (pin "3") (pinfunction "3_3") (pintype "passive"))
      (node (ref "J2") (pin "4") (pinfunction "4_4") (pintype "passive"))
      (node (ref "R10") (pin "1") (pinfunction "1_1") (pintype "passive"))
      (node (ref "U1") (pin "8") (pinfunction "-IN_8") (pintype "input"))
    )
    (net (code "18") (name "THER2-SIG") (class "Default")
      (node (ref "J11") (pin "5") (pinfunction "5_5") (pintype "bidirectional"))
      (node (ref "R14") (pin "1") (pinfunction "1_1") (pintype "passive"))
      (node (ref "R18") (pin "1") (pinfunction "1_1") (pintype "passive"))
      (node (ref "U1") (pin "14") (pinfunction "OUT_14") (pintype "output"))
    )
    (net (code "19") (name "THER3-IN") (class "Default")
      (node (ref "CR3") (pin "3") (pinfunction "3_3") (pintype "passive"))
      (node (ref "J3") (pin "4") (pinfunction "4_4") (pintype "passive"))
      (node (ref "R11") (pin "1") (pinfunction "1_1") (pintype "passive"))
      (node (ref "U1") (pin "6") (pinfunction "-IN_6") (pintype "input"))
    )
    (net (code "20") (name "THER3-SIG") (class "Default")
      (node (ref "J11") (pin "6") (pinfunction "6_6") (pintype "bidirectional"))
      (node (ref "R15") (pin "1") (pinfunction "1_1") (pintype "passive"))
      (node (ref "R19") (pin "1") (pinfunction "1_1") (pintype "passive"))
      (node (ref "U1") (pin "1") (pinfunction "OUT_1") (pintype "output"))
    )
    (net (code "21") (name "THER4-IN") (class "Default")
      (node (ref "CR4") (pin "3") (pinfunction "3_3") (pintype "passive"))
      (node (ref "J4") (pin "4") (pinfunction "4_4") (pintype "passive"))
      (node (ref "R12") (pin "1") (pinfunction "1_1") (pintype "passive"))
      (node (ref "U1") (pin "4") (pinfunction "-IN_4") (pintype "input"))
    )
    (net (code "22") (name "THER4-SIG") (class "Default")
      (node (ref "J11") (pin "1") (pinfunction "1_1") (pintype "bidirectional"))
      (node (ref "R16") (pin "1") (pinfunction "1_1") (pintype "passive"))
      (node (ref "R20") (pin "1") (pinfunction "1_1") (pintype "passive"))
      (node (ref "U1") (pin "2") (pinfunction "OUT_2") (pintype "output"))
    )
    (net (code "23") (name "THER5-IN") (class "Default")
      (node (ref "CR5") (pin "3") (pinfunction "3_3") (pintype "passive"))
      (node (ref "J5") (pin "4") (pinfunction "4_4") (pintype "passive"))
      (node (ref "R27") (pin "1") (pinfunction "1_1") (pintype "passive"))
      (node (ref "U2") (pin "8") (pinfunction "-IN_8") (pintype "input"))
    )
    (net (code "24") (name "THER5-SIG") (class "Default")
      (node (ref "J11") (pin "7") (pinfunction "7_7") (pintype "bidirectional"))
      (node (ref "R30") (pin "1") (pinfunction "1_1") (pintype "passive"))
      (node (ref "R33") (pin "1") (pinfunction "1_1") (pintype "passive"))
      (node (ref "U2") (pin "14") (pinfunction "OUT_14") (pintype "output"))
    )
    (net (code "25") (name "THER6-IN") (class "Default")
      (node (ref "CR6") (pin "3") (pinfunction "3_3") (pintype "passive"))
      (node (ref "J6") (pin "4") (pinfunction "4_4") (pintype "passive"))
      (node (ref "R28") (pin "1") (pinfunction "1_1") (pintype "passive"))
      (node (ref "U2") (pin "6") (pinfunction "-IN_6") (pintype "input"))
    )
    (net (code "26") (name "THER6-SIG") (class "Default")
      (node (ref "J11") (pin "9") (pinfunction "9_9") (pintype "bidirectional"))
      (node (ref "R31") (pin "1") (pinfunction "1_1") (pintype "passive"))
      (node (ref "R34") (pin "1") (pinfunction "1_1") (pintype "passive"))
      (node (ref "U2") (pin "1") (pinfunction "OUT_1") (pintype "output"))
    )
    (net (code "27") (name "THER7-IN") (class "Default")
      (node (ref "CR7") (pin "3") (pinfunction "3_3") (pintype "passive"))
      (node (ref "J7") (pin "4") (pinfunction "4_4") (pintype "passive"))
      (node (ref "R29") (pin "1") (pinfunction "1_1") (pintype "passive"))
      (node (ref "U2") (pin "4") (pinfunction "-IN_4") (pintype "input"))
    )
    (net (code "28") (name "THER7-SIG") (class "Default")
      (node (ref "J11") (pin "8") (pinfunction "8_8") (pintype "bidirectional"))
      (node (ref "R32") (pin "1") (pinfunction "1_1") (pintype "passive"))
      (node (ref "R35") (pin "1") (pinfunction "1_1") (pintype "passive"))
      (node (ref "U2") (pin "2") (pinfunction "OUT_2") (pintype "output"))
    )
    (net (code "29") (name "THER8-IN") (class "Default")
      (node (ref "CR8") (pin "3") (pinfunction "3_3") (pintype "passive"))
      (node (ref "J8") (pin "4") (pinfunction "4_4") (pintype "passive"))
      (node (ref "R42") (pin "1") (pinfunction "1_1") (pintype "passive"))
      (node (ref "U3") (pin "8") (pinfunction "-IN_8") (pintype "input"))
    )
    (net (code "30") (name "THER8-SIG") (class "Default")
      (node (ref "J11") (pin "10") (pinfunction "10_10") (pintype "bidirectional"))
      (node (ref "R45") (pin "1") (pinfunction "1_1") (pintype "passive"))
      (node (ref "R48") (pin "1") (pinfunction "1_1") (pintype "passive"))
      (node (ref "U3") (pin "14") (pinfunction "OUT_14") (pintype "output"))
    )
    (net (code "31") (name "THER9-IN") (class "Default")
      (node (ref "CR9") (pin "3") (pinfunction "3_3") (pintype "passive"))
      (node (ref "J9") (pin "4") (pinfunction "4_4") (pintype "passive"))
      (node (ref "R43") (pin "1") (pinfunction "1_1") (pintype "passive"))
      (node (ref "U3") (pin "6") (pinfunction "-IN_6") (pintype "input"))
    )
    (net (code "32") (name "THER9-SIG") (class "Default")
      (node (ref "J11") (pin "11") (pinfunction "11_11") (pintype "bidirectional"))
      (node (ref "R46") (pin "1") (pinfunction "1_1") (pintype "passive"))
      (node (ref "R49") (pin "1") (pinfunction "1_1") (pintype "passive"))
      (node (ref "U3") (pin "1") (pinfunction "OUT_1") (pintype "output"))
    )
    (net (code "33") (name "THER10-IN") (class "Default")
      (node (ref "CR10") (pin "3") (pinfunction "3_3") (pintype "passive"))
      (node (ref "J10") (pin "4") (pinfunction "4_4") (pintype "passive"))
      (node (ref "R44") (pin "1") (pinfunction "1_1") (pintype "passive"))
      (node (ref "U3") (pin "4") (pinfunction "-IN_4") (pintype "input"))
    )
    (net (code "34") (name "THER10-SIG") (class "Default")
      (node (ref "J11") (pin "12") (pinfunction "12_12") (pintype "bidirectional"))
      (node (ref "R47") (pin "1") (pinfunction "1_1") (pintype "passive"))
      (node (ref "R50") (pin "1") (pinfunction "1_1") (pintype "passive"))
      (node (ref "U3") (pin "2") (pinfunction "OUT_2") (pintype "output"))
    )
    (net (code "35") (name "unconnected-(CR1-NC-Pad2)") (class "Default")
      (node (ref "CR1") (pin "2") (pinfunction "NC_2") (pintype "no_connect"))
    )
    (net (code "36") (name "unconnected-(CR2-NC-Pad2)") (class "Default")
      (node (ref "CR2") (pin "2") (pinfunction "NC_2") (pintype "no_connect"))
    )
    (net (code "37") (name "unconnected-(CR3-NC-Pad2)") (class "Default")
      (node (ref "CR3") (pin "2") (pinfunction "NC_2") (pintype "no_connect"))
    )
    (net (code "38") (name "unconnected-(CR4-NC-Pad2)") (class "Default")
      (node (ref "CR4") (pin "2") (pinfunction "NC_2") (pintype "no_connect"))
    )
    (net (code "39") (name "unconnected-(CR5-NC-Pad2)") (class "Default")
      (node (ref "CR5") (pin "2") (pinfunction "NC_2") (pintype "no_connect"))
    )
    (net (code "40") (name "unconnected-(CR6-NC-Pad2)") (class "Default")
      (node (ref "CR6") (pin "2") (pinfunction "NC_2") (pintype "no_connect"))
    )
    (net (code "41") (name "unconnected-(CR7-NC-Pad2)") (class "Default")
      (node (ref "CR7") (pin "2") (pinfunction "NC_2") (pintype "no_connect"))
    )
    (net (code "42") (name "unconnected-(CR8-NC-Pad2)") (class "Default")
      (node (ref "CR8") (pin "2") (pinfunction "NC_2") (pintype "no_connect"))
    )
    (net (code "43") (name "unconnected-(CR9-NC-Pad2)") (class "Default")
      (node (ref "CR9") (pin "2") (pinfunction "NC_2") (pintype "no_connect"))
    )
    (net (code "44") (name "unconnected-(CR10-NC-Pad2)") (class "Default")
      (node (ref "CR10") (pin "2") (pinfunction "NC_2") (pintype "no_connect"))
    )
    (net (code "45") (name "unconnected-(J1-SHIELD-PadS1)") (class "Default")
      (node (ref "J1") (pin "S1") (pinfunction "SHIELD_S1") (pintype "passive"))
    )
    (net (code "46") (name "unconnected-(J2-SHIELD-PadS1)") (class "Default")
      (node (ref "J2") (pin "S1") (pinfunction "SHIELD_S1") (pintype "passive"))
    )
    (net (code "47") (name "unconnected-(J3-SHIELD-PadS1)") (class "Default")
      (node (ref "J3") (pin "S1") (pinfunction "SHIELD_S1") (pintype "passive"))
    )
    (net (code "48") (name "unconnected-(J4-SHIELD-PadS1)") (class "Default")
      (node (ref "J4") (pin "S1") (pinfunction "SHIELD_S1") (pintype "passive"))
    )
    (net (code "49") (name "unconnected-(J5-SHIELD-PadS1)") (class "Default")
      (node (ref "J5") (pin "S1") (pinfunction "SHIELD_S1") (pintype "passive"))
    )
    (net (code "50") (name "unconnected-(J6-SHIELD-PadS1)") (class "Default")
      (node (ref "J6") (pin "S1") (pinfunction "SHIELD_S1") (pintype "passive"))
    )
    (net (code "51") (name "unconnected-(J7-SHIELD-PadS1)") (class "Default")
      (node (ref "J7") (pin "S1") (pinfunction "SHIELD_S1") (pintype "passive"))
    )
    (net (code "52") (name "unconnected-(J8-SHIELD-PadS1)") (class "Default")
      (node (ref "J8") (pin "S1") (pinfunction "SHIELD_S1") (pintype "passive"))
    )
    (net (code "53") (name "unconnected-(J9-SHIELD-PadS1)") (class "Default")
      (node (ref "J9") (pin "S1") (pinfunction "SHIELD_S1") (pintype "passive"))
    )
    (net (code "54") (name "unconnected-(J10-SHIELD-PadS1)") (class "Default")
      (node (ref "J10") (pin "S1") (pinfunction "SHIELD_S1") (pintype "passive"))
    )
  )
)
